# Elevator_LeTrungHieu.net
KiCad netlist of a schematic drawn in Altium Designer
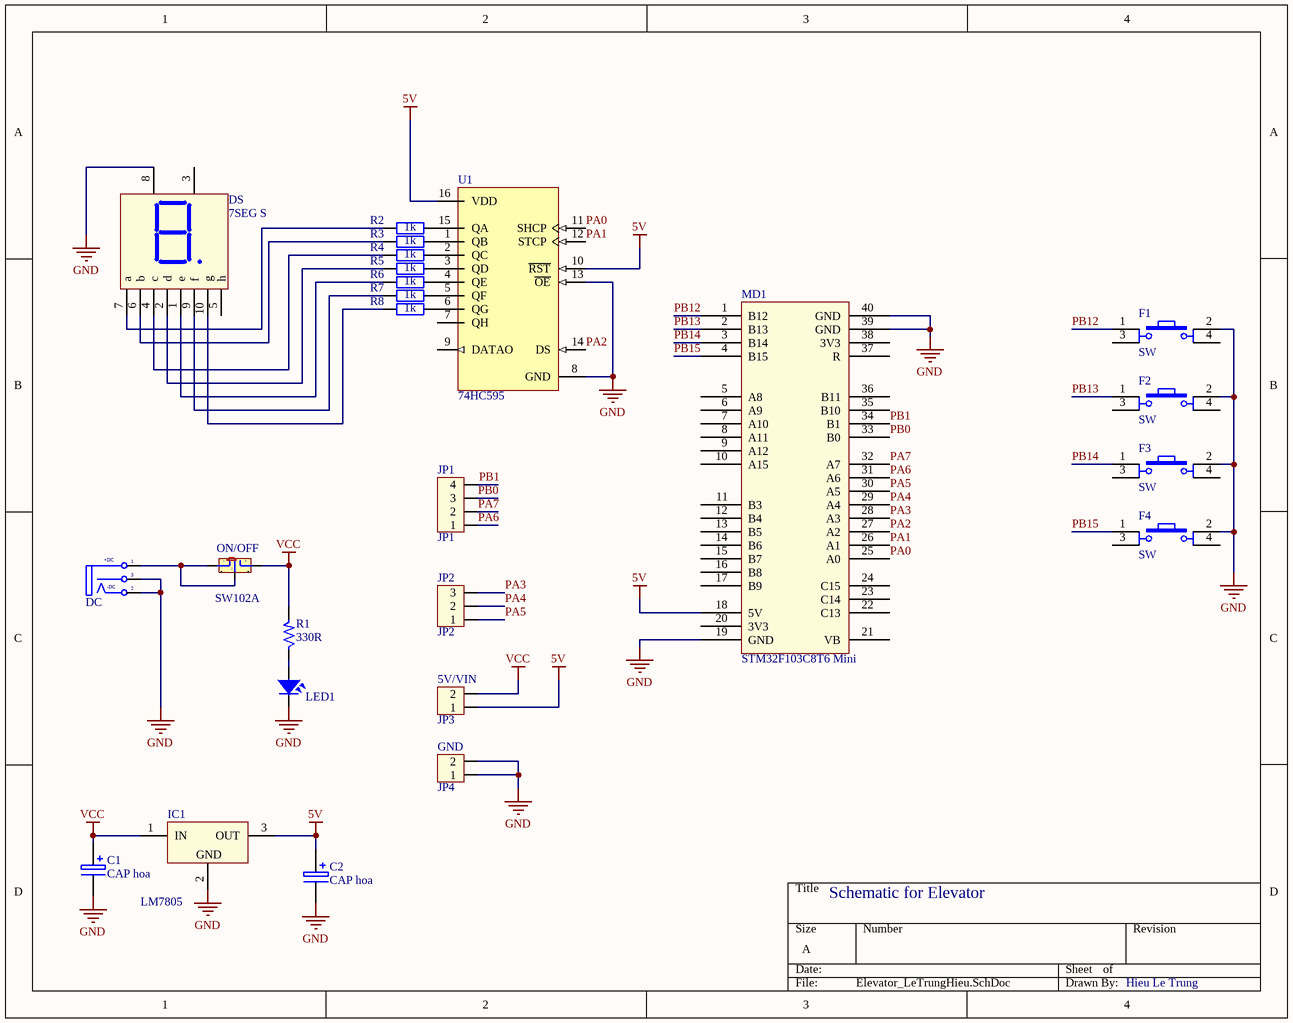
[diagram p0: Elevator_LeTrungHieu.SchDoc]

(export (version "E")
  (design (tool "Eeschema 10.0.6"))
  (components
    (comp (ref "5V/VIN")
      (value "JP3")
      (footprint "jam2")
      (description "jam 2")
      (libsource (lib "myLibrary") (part "Jam 2"))
    )
    (comp (ref "C1")
      (value "CAP hoa")
      (footprint "CP2/4")
      (description "Cap")
      (libsource (lib "myLibrary") (part "CAP hoa"))
    )
    (comp (ref "C2")
      (value "CAP hoa")
      (footprint "CP2/4")
      (description "Cap")
      (libsource (lib "myLibrary") (part "CAP hoa"))
    )
    (comp (ref "DC") (value "POWER") (footprint "DC5.5*2.1") (libsource (lib "myLibrary") (part "DCIN")))
    (comp (ref "DS")
      (value "7SEG S")
      (footprint "7SEGS")
      (description "Single 7 Seg Dipslay")
      (libsource (lib "myLibrary") (part "LED7S"))
    )
    (comp (ref "F1")
      (value "SW")
      (footprint "SW4")
      (description "Switch button 4 pin")
      (libsource (lib "SCH_MyLib_0") (part "SW4"))
    )
    (comp (ref "F2")
      (value "SW")
      (footprint "SW4")
      (description "Switch button 4 pin")
      (libsource (lib "SCH_MyLib_0") (part "SW4"))
    )
    (comp (ref "F3")
      (value "SW")
      (footprint "SW4")
      (description "Switch button 4 pin")
      (libsource (lib "SCH_MyLib_0") (part "SW4"))
    )
    (comp (ref "F4")
      (value "SW")
      (footprint "SW4")
      (description "Switch button 4 pin")
      (libsource (lib "SCH_MyLib_0") (part "SW4"))
    )
    (comp (ref "GND")
      (value "JP4")
      (footprint "jam2")
      (description "jam 2")
      (libsource (lib "myLibrary") (part "Jam 2"))
    )
    (comp (ref "IC1")
      (value "LM7805")
      (footprint "QTO-220")
      (description "On ap +, from + 5 to + 24VDC")
      (libsource (lib "myLibrary") (part "LM78xx"))
    )
    (comp (ref "JP1")
      (value "JP1")
      (footprint "jam4")
      (description "jam 4")
      (libsource (lib "myLibrary") (part "jam 4"))
    )
    (comp (ref "JP2")
      (value "JP2")
      (footprint "jam3")
      (description "jam 3")
      (libsource (lib "myLibrary") (part "jam 3"))
    )
    (comp (ref "LED1")
      (value "LED")
      (footprint "LED-5-BLUE")
      (description "LED Single colour Green and Red")
      (libsource (lib "myLibrary") (part "LED_1"))
    )
    (comp (ref "MD1")
      (value "STM32F103C8T6 Mini")
      (footprint "STM32F103C8T6 Mini")
      (libsource (lib "myLibrary") (part "STM32F103C8T6 Mini"))
    )
    (comp (ref "ON/OFF")
      (value "SW102A")
      (footprint "SW102")
      (description "Switch 102 on Broad")
      (libsource (lib "myLibrary") (part "SW102A"))
    )
    (comp (ref "R1")
      (value "330R")
      (footprint "R1/4W")
      (description "Res")
      (libsource (lib "myLibrary") (part "Res"))
    )
    (comp (ref "R2")
      (value "1k")
      (footprint "SM-RES-0805")
      (description "Resistor 1/4W")
      (libsource (lib "myLibrary") (part "R1/4W"))
    )
    (comp (ref "R3")
      (value "1k")
      (footprint "SM-RES-0805")
      (description "Resistor 1/4W")
      (libsource (lib "myLibrary") (part "R1/4W"))
    )
    (comp (ref "R4")
      (value "1k")
      (footprint "SM-RES-0805")
      (description "Resistor 1/4W")
      (libsource (lib "myLibrary") (part "R1/4W"))
    )
    (comp (ref "R5")
      (value "1k")
      (footprint "SM-RES-0805")
      (description "Resistor 1/4W")
      (libsource (lib "myLibrary") (part "R1/4W"))
    )
    (comp (ref "R6")
      (value "1k")
      (footprint "SM-RES-0805")
      (description "Resistor 1/4W")
      (libsource (lib "myLibrary") (part "R1/4W"))
    )
    (comp (ref "R7")
      (value "1k")
      (footprint "SM-RES-0805")
      (description "Resistor 1/4W")
      (libsource (lib "myLibrary") (part "R1/4W"))
    )
    (comp (ref "R8")
      (value "1k")
      (footprint "SM-RES-0805")
      (description "Resistor 1/4W")
      (libsource (lib "myLibrary") (part "R1/4W"))
    )
    (comp (ref "U1")
      (value "74HC595")
      (footprint "DIP16")
      (description "8-Bit Serial-Input/Serial or Prallel-Output Shift Register with Latched 3-State Outputs")
      (fields (field (name "PUBLISHER") "Altium Limited"))
      (libsource (lib "Devzone_SCHLib") (part "74HC595"))
    )
  )
  (nets
    (net (code "1") (name "/PA0") (class "Default")
      (node (ref "MD1") (pin "25") (pinfunction "A0_25") (pintype "passive"))
      (node (ref "U1") (pin "11") (pinfunction "SHCP_11") (pintype "input"))
    )
    (net (code "2") (name "/PA1") (class "Default")
      (node (ref "MD1") (pin "26") (pinfunction "A1_26") (pintype "passive"))
      (node (ref "U1") (pin "12") (pinfunction "STCP_12") (pintype "input"))
    )
    (net (code "3") (name "/PA2") (class "Default")
      (node (ref "MD1") (pin "27") (pinfunction "A2_27") (pintype "passive"))
      (node (ref "U1") (pin "14") (pinfunction "DS_14") (pintype "input"))
    )
    (net (code "4") (name "/PA3") (class "Default")
      (node (ref "JP2") (pin "3") (pinfunction "3_3") (pintype "passive"))
      (node (ref "MD1") (pin "28") (pinfunction "A3_28") (pintype "passive"))
    )
    (net (code "5") (name "/PA4") (class "Default")
      (node (ref "JP2") (pin "2") (pinfunction "2_2") (pintype "passive"))
      (node (ref "MD1") (pin "29") (pinfunction "A4_29") (pintype "passive"))
    )
    (net (code "6") (name "/PA5") (class "Default")
      (node (ref "JP2") (pin "1") (pinfunction "1_1") (pintype "passive"))
      (node (ref "MD1") (pin "30") (pinfunction "A5_30") (pintype "passive"))
    )
    (net (code "7") (name "/PA6") (class "Default")
      (node (ref "JP1") (pin "1") (pinfunction "1_1") (pintype "passive"))
      (node (ref "MD1") (pin "31") (pinfunction "A6_31") (pintype "passive"))
    )
    (net (code "8") (name "/PA7") (class "Default")
      (node (ref "JP1") (pin "2") (pinfunction "2_2") (pintype "passive"))
      (node (ref "MD1") (pin "32") (pinfunction "A7_32") (pintype "passive"))
    )
    (net (code "9") (name "/PB0") (class "Default")
      (node (ref "JP1") (pin "3") (pinfunction "3_3") (pintype "passive"))
      (node (ref "MD1") (pin "33") (pinfunction "B0_33") (pintype "passive"))
    )
    (net (code "10") (name "/PB1") (class "Default")
      (node (ref "JP1") (pin "4") (pinfunction "4_4") (pintype "passive"))
      (node (ref "MD1") (pin "34") (pinfunction "B1_34") (pintype "passive"))
    )
    (net (code "11") (name "/PB12") (class "Default")
      (node (ref "F1") (pin "1") (pintype "passive"))
      (node (ref "MD1") (pin "1") (pinfunction "B12_1") (pintype "passive"))
    )
    (net (code "12") (name "/PB13") (class "Default")
      (node (ref "F2") (pin "1") (pintype "passive"))
      (node (ref "MD1") (pin "2") (pinfunction "B13_2") (pintype "passive"))
    )
    (net (code "13") (name "/PB14") (class "Default")
      (node (ref "F3") (pin "1") (pintype "passive"))
      (node (ref "MD1") (pin "3") (pinfunction "B14_3") (pintype "passive"))
    )
    (net (code "14") (name "/PB15") (class "Default")
      (node (ref "F4") (pin "1") (pintype "passive"))
      (node (ref "MD1") (pin "4") (pinfunction "B15_4") (pintype "passive"))
    )
    (net (code "15") (name "5V") (class "Default")
      (node (ref "5V/VIN") (pin "1") (pinfunction "1_1") (pintype "passive"))
      (node (ref "C2") (pin "1") (pintype "passive"))
      (node (ref "IC1") (pin "3") (pinfunction "OUT_3") (pintype "passive"))
      (node (ref "MD1") (pin "18") (pinfunction "5V_18") (pintype "passive"))
      (node (ref "U1") (pin "10") (pinfunction "~{RST}_10") (pintype "input"))
      (node (ref "U1") (pin "16") (pinfunction "VDD_16") (pintype "power_in"))
    )
    (net (code "16") (name "GND") (class "Default")
      (node (ref "C1") (pin "2") (pintype "passive"))
      (node (ref "C2") (pin "2") (pintype "passive"))
      (node (ref "DC") (pin "2") (pinfunction "TN_2") (pintype "passive"))
      (node (ref "DC") (pin "3") (pinfunction "S_3") (pintype "power_in"))
      (node (ref "DS") (pin "8") (pinfunction "Vcc_8") (pintype "passive"))
      (node (ref "F1") (pin "2") (pintype "passive"))
      (node (ref "F2") (pin "2") (pintype "passive"))
      (node (ref "F3") (pin "2") (pintype "passive"))
      (node (ref "F4") (pin "2") (pintype "passive"))
      (node (ref "GND") (pin "1") (pinfunction "1_1") (pintype "passive"))
      (node (ref "GND") (pin "2") (pinfunction "2_2") (pintype "passive"))
      (node (ref "IC1") (pin "2") (pinfunction "GND_2") (pintype "passive"))
      (node (ref "LED1") (pin "2") (pinfunction "2_2") (pintype "passive"))
      (node (ref "MD1") (pin "19") (pinfunction "GND_19") (pintype "passive"))
      (node (ref "MD1") (pin "39") (pinfunction "GND_39") (pintype "passive"))
      (node (ref "MD1") (pin "40") (pinfunction "GND_40") (pintype "passive"))
      (node (ref "U1") (pin "13") (pinfunction "~{OE}_13") (pintype "input"))
      (node (ref "U1") (pin "8") (pinfunction "GND_8") (pintype "power_in"))
    )
    (net (code "17") (name "Net-(DC-T)") (class "Default")
      (node (ref "DC") (pin "1") (pinfunction "T_1") (pintype "passive"))
      (node (ref "ON/OFF") (pin "1") (pinfunction "1_1") (pintype "passive"))
      (node (ref "ON/OFF") (pin "2") (pinfunction "2_2") (pintype "passive"))
    )
    (net (code "18") (name "Net-(DS-a)") (class "Default")
      (node (ref "DS") (pin "7") (pinfunction "a_7") (pintype "passive"))
      (node (ref "R2") (pin "1") (pinfunction "1_1") (pintype "passive"))
    )
    (net (code "19") (name "Net-(DS-b)") (class "Default")
      (node (ref "DS") (pin "6") (pinfunction "b_6") (pintype "passive"))
      (node (ref "R3") (pin "1") (pinfunction "1_1") (pintype "passive"))
    )
    (net (code "20") (name "Net-(DS-c)") (class "Default")
      (node (ref "DS") (pin "4") (pinfunction "c_4") (pintype "passive"))
      (node (ref "R4") (pin "1") (pinfunction "1_1") (pintype "passive"))
    )
    (net (code "21") (name "Net-(DS-d)") (class "Default")
      (node (ref "DS") (pin "2") (pinfunction "d_2") (pintype "passive"))
      (node (ref "R5") (pin "1") (pinfunction "1_1") (pintype "passive"))
    )
    (net (code "22") (name "Net-(DS-e)") (class "Default")
      (node (ref "DS") (pin "1") (pinfunction "e_1") (pintype "passive"))
      (node (ref "R6") (pin "1") (pinfunction "1_1") (pintype "passive"))
    )
    (net (code "23") (name "Net-(DS-f)") (class "Default")
      (node (ref "DS") (pin "9") (pinfunction "f_9") (pintype "passive"))
      (node (ref "R7") (pin "1") (pinfunction "1_1") (pintype "passive"))
    )
    (net (code "24") (name "Net-(DS-g)") (class "Default")
      (node (ref "DS") (pin "10") (pinfunction "g_10") (pintype "passive"))
      (node (ref "R8") (pin "1") (pinfunction "1_1") (pintype "passive"))
    )
    (net (code "25") (name "Net-(LED1-Pad1)") (class "Default")
      (node (ref "LED1") (pin "1") (pinfunction "1_1") (pintype "passive"))
      (node (ref "R1") (pin "1") (pinfunction "1_1") (pintype "passive"))
    )
    (net (code "26") (name "Net-(U1-QA)") (class "Default")
      (node (ref "R2") (pin "2") (pinfunction "2_2") (pintype "passive"))
      (node (ref "U1") (pin "15") (pinfunction "QA_15") (pintype "tri_state"))
    )
    (net (code "27") (name "Net-(U1-QB)") (class "Default")
      (node (ref "R3") (pin "2") (pinfunction "2_2") (pintype "passive"))
      (node (ref "U1") (pin "1") (pinfunction "QB_1") (pintype "tri_state"))
    )
    (net (code "28") (name "Net-(U1-QC)") (class "Default")
      (node (ref "R4") (pin "2") (pinfunction "2_2") (pintype "passive"))
      (node (ref "U1") (pin "2") (pinfunction "QC_2") (pintype "tri_state"))
    )
    (net (code "29") (name "Net-(U1-QD)") (class "Default")
      (node (ref "R5") (pin "2") (pinfunction "2_2") (pintype "passive"))
      (node (ref "U1") (pin "3") (pinfunction "QD_3") (pintype "tri_state"))
    )
    (net (code "30") (name "Net-(U1-QE)") (class "Default")
      (node (ref "R6") (pin "2") (pinfunction "2_2") (pintype "passive"))
      (node (ref "U1") (pin "4") (pinfunction "QE_4") (pintype "tri_state"))
    )
    (net (code "31") (name "Net-(U1-QF)") (class "Default")
      (node (ref "R7") (pin "2") (pinfunction "2_2") (pintype "passive"))
      (node (ref "U1") (pin "5") (pinfunction "QF_5") (pintype "tri_state"))
    )
    (net (code "32") (name "Net-(U1-QG)") (class "Default")
      (node (ref "R8") (pin "2") (pinfunction "2_2") (pintype "passive"))
      (node (ref "U1") (pin "6") (pinfunction "QG_6") (pintype "tri_state"))
    )
    (net (code "33") (name "VCC") (class "Default")
      (node (ref "5V/VIN") (pin "2") (pinfunction "2_2") (pintype "passive"))
      (node (ref "C1") (pin "1") (pintype "passive"))
      (node (ref "IC1") (pin "1") (pinfunction "IN_1") (pintype "passive"))
      (node (ref "ON/OFF") (pin "3") (pinfunction "3_3") (pintype "passive"))
      (node (ref "R1") (pin "2") (pinfunction "2_2") (pintype "passive"))
    )
    (net (code "34") (name "unconnected-(DS-Vcc-Pad3)") (class "Default")
      (node (ref "DS") (pin "3") (pinfunction "Vcc_3") (pintype "passive"))
    )
    (net (code "35") (name "unconnected-(DS-h-Pad5)") (class "Default")
      (node (ref "DS") (pin "5") (pinfunction "h_5") (pintype "passive"))
    )
    (net (code "36") (name "unconnected-(F1-Pad3)") (class "Default")
      (node (ref "F1") (pin "3") (pintype "passive"))
    )
    (net (code "37") (name "unconnected-(F1-Pad4)") (class "Default")
      (node (ref "F1") (pin "4") (pintype "passive"))
    )
    (net (code "38") (name "unconnected-(F2-Pad3)") (class "Default")
      (node (ref "F2") (pin "3") (pintype "passive"))
    )
    (net (code "39") (name "unconnected-(F2-Pad4)") (class "Default")
      (node (ref "F2") (pin "4") (pintype "passive"))
    )
    (net (code "40") (name "unconnected-(F3-Pad3)") (class "Default")
      (node (ref "F3") (pin "3") (pintype "passive"))
    )
    (net (code "41") (name "unconnected-(F3-Pad4)") (class "Default")
      (node (ref "F3") (pin "4") (pintype "passive"))
    )
    (net (code "42") (name "unconnected-(F4-Pad3)") (class "Default")
      (node (ref "F4") (pin "3") (pintype "passive"))
    )
    (net (code "43") (name "unconnected-(F4-Pad4)") (class "Default")
      (node (ref "F4") (pin "4") (pintype "passive"))
    )
    (net (code "44") (name "unconnected-(MD1-3V3-Pad20)") (class "Default")
      (node (ref "MD1") (pin "20") (pinfunction "3V3_20") (pintype "passive"))
    )
    (net (code "45") (name "unconnected-(MD1-3V3-Pad38)") (class "Default")
      (node (ref "MD1") (pin "38") (pinfunction "3V3_38") (pintype "passive"))
    )
    (net (code "46") (name "unconnected-(MD1-A8-Pad5)") (class "Default")
      (node (ref "MD1") (pin "5") (pinfunction "A8_5") (pintype "passive"))
    )
    (net (code "47") (name "unconnected-(MD1-A9-Pad6)") (class "Default")
      (node (ref "MD1") (pin "6") (pinfunction "A9_6") (pintype "passive"))
    )
    (net (code "48") (name "unconnected-(MD1-A10-Pad7)") (class "Default")
      (node (ref "MD1") (pin "7") (pinfunction "A10_7") (pintype "passive"))
    )
    (net (code "49") (name "unconnected-(MD1-A11-Pad8)") (class "Default")
      (node (ref "MD1") (pin "8") (pinfunction "A11_8") (pintype "passive"))
    )
    (net (code "50") (name "unconnected-(MD1-A12-Pad9)") (class "Default")
      (node (ref "MD1") (pin "9") (pinfunction "A12_9") (pintype "passive"))
    )
    (net (code "51") (name "unconnected-(MD1-A15-Pad10)") (class "Default")
      (node (ref "MD1") (pin "10") (pinfunction "A15_10") (pintype "passive"))
    )
    (net (code "52") (name "unconnected-(MD1-B3-Pad11)") (class "Default")
      (node (ref "MD1") (pin "11") (pinfunction "B3_11") (pintype "passive"))
    )
    (net (code "53") (name "unconnected-(MD1-B4-Pad12)") (class "Default")
      (node (ref "MD1") (pin "12") (pinfunction "B4_12") (pintype "passive"))
    )
    (net (code "54") (name "unconnected-(MD1-B5-Pad13)") (class "Default")
      (node (ref "MD1") (pin "13") (pinfunction "B5_13") (pintype "passive"))
    )
    (net (code "55") (name "unconnected-(MD1-B6-Pad14)") (class "Default")
      (node (ref "MD1") (pin "14") (pinfunction "B6_14") (pintype "passive"))
    )
    (net (code "56") (name "unconnected-(MD1-B7-Pad15)") (class "Default")
      (node (ref "MD1") (pin "15") (pinfunction "B7_15") (pintype "passive"))
    )
    (net (code "57") (name "unconnected-(MD1-B8-Pad16)") (class "Default")
      (node (ref "MD1") (pin "16") (pinfunction "B8_16") (pintype "passive"))
    )
    (net (code "58") (name "unconnected-(MD1-B9-Pad17)") (class "Default")
      (node (ref "MD1") (pin "17") (pinfunction "B9_17") (pintype "passive"))
    )
    (net (code "59") (name "unconnected-(MD1-B10-Pad35)") (class "Default")
      (node (ref "MD1") (pin "35") (pinfunction "B10_35") (pintype "passive"))
    )
    (net (code "60") (name "unconnected-(MD1-B11-Pad36)") (class "Default")
      (node (ref "MD1") (pin "36") (pinfunction "B11_36") (pintype "passive"))
    )
    (net (code "61") (name "unconnected-(MD1-C13-Pad22)") (class "Default")
      (node (ref "MD1") (pin "22") (pinfunction "C13_22") (pintype "passive"))
    )
    (net (code "62") (name "unconnected-(MD1-C14-Pad23)") (class "Default")
      (node (ref "MD1") (pin "23") (pinfunction "C14_23") (pintype "passive"))
    )
    (net (code "63") (name "unconnected-(MD1-C15-Pad24)") (class "Default")
      (node (ref "MD1") (pin "24") (pinfunction "C15_24") (pintype "passive"))
    )
    (net (code "64") (name "unconnected-(MD1-R-Pad37)") (class "Default")
      (node (ref "MD1") (pin "37") (pinfunction "R_37") (pintype "passive"))
    )
    (net (code "65") (name "unconnected-(MD1-VB-Pad21)") (class "Default")
      (node (ref "MD1") (pin "21") (pinfunction "VB_21") (pintype "passive"))
    )
    (net (code "66") (name "unconnected-(ON/OFF-Pad4)") (class "Default")
      (node (ref "ON/OFF") (pin "4") (pinfunction "4_4") (pintype "passive"))
    )
    (net (code "67") (name "unconnected-(ON/OFF-Pad5)") (class "Default")
      (node (ref "ON/OFF") (pin "5") (pinfunction "5_5") (pintype "passive"))
    )
    (net (code "68") (name "unconnected-(U1-DATAO-Pad9)") (class "Default")
      (node (ref "U1") (pin "9") (pinfunction "DATAO_9") (pintype "output"))
    )
    (net (code "69") (name "unconnected-(U1-QH-Pad7)") (class "Default")
      (node (ref "U1") (pin "7") (pinfunction "QH_7") (pintype "tri_state"))
    )
  )
)
